# ETRX_Shield.net
KiCad netlist of a schematic drawn in Altium Designer
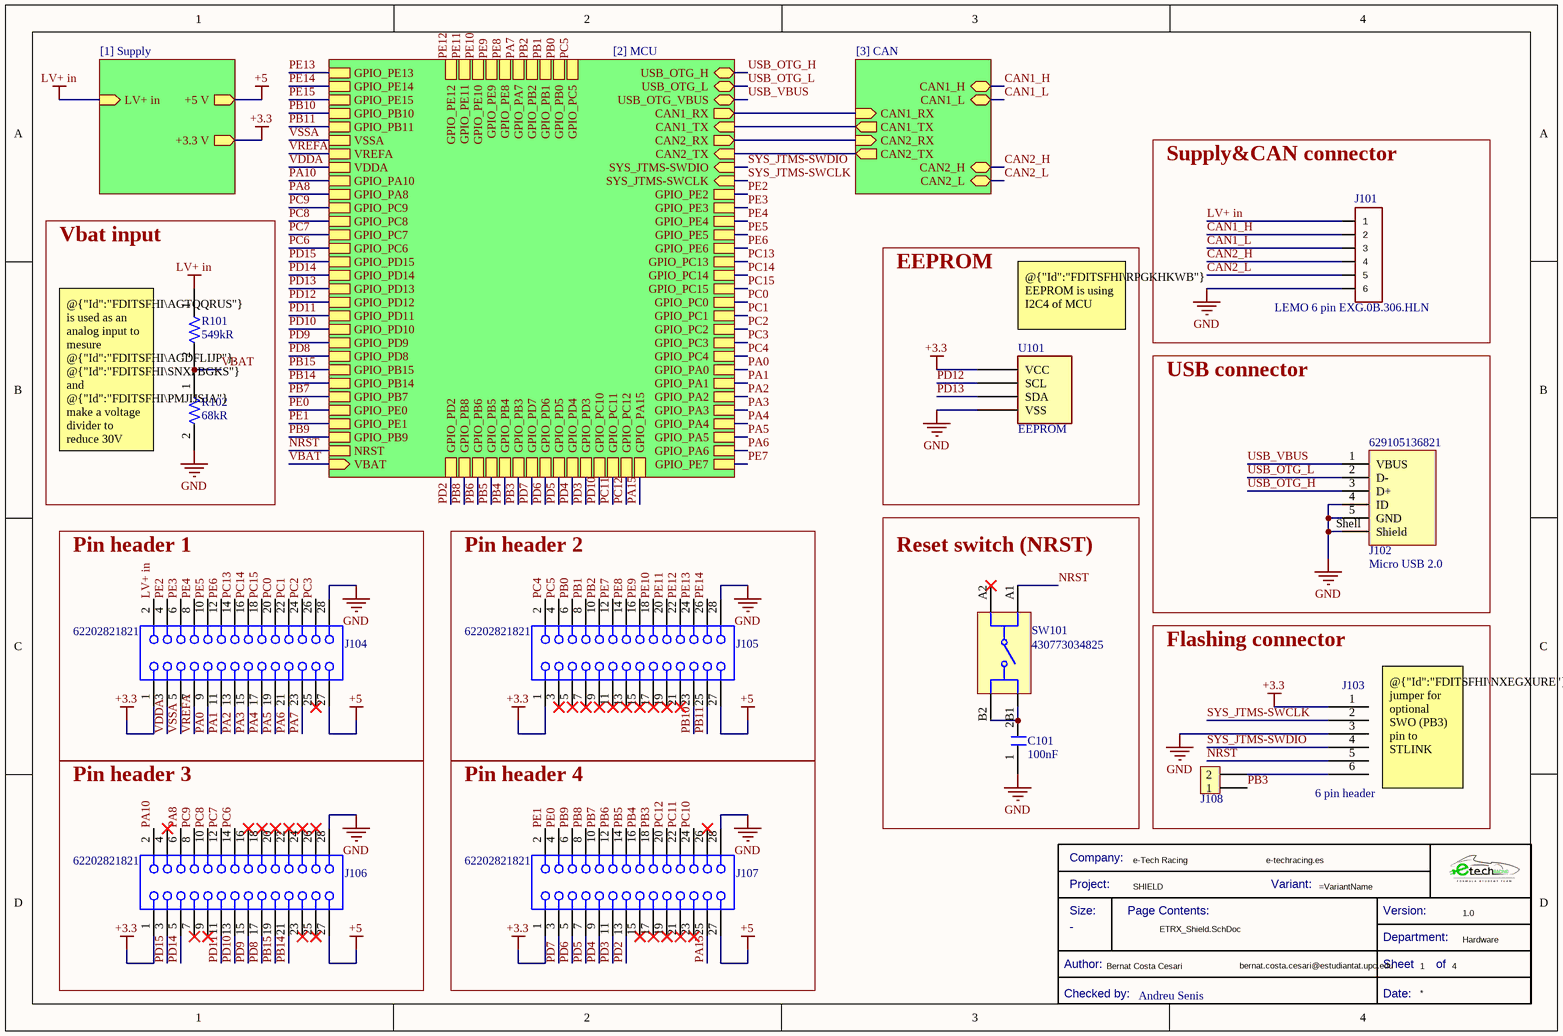
[diagram p0: ETRX_Shield.SchDoc]

(export (version "E")
  (design (tool "Eeschema 10.0.6"))
  (components
    (comp (ref "*")
      (value "Title Block_template")
      (description "Standard Title Block")
      (fields
        (field (name "SIZE") "-")
        (field (name ".CREATOR") "GP")
        (field (name ".PCBCHECK") "GP")
        (field (name ".SCHCHECK") "GP")
      )
      (libsource (lib "e-Tech_Racing") (part "Title Block_template"))
    )
    (comp (ref "C101")
      (value "885012208058")
      (footprint "C1206FNPC-RW")
      (description "Cap Cer 0.1UF 25V X7R 1206")
      (fields
        (field (name "MANUFACTURER") "Wurth Electronics")
        (field (name "TOLERANCE") "10%")
        (field (name "CAPACITANCE") "100nF")
        (field (name ".CREATOR") "DO")
      )
      (libsource (lib "Passives") (part "C100n-25V-1206FNPC-X7R"))
    )
    (comp (ref "J101")
      (value "LEMO 6 pin EXG.0B.306.HLN")
      (footprint "EXG.0B.306.HLN")
      (fields (field (name "MPN") "EXG.0B.306.HLN"))
      (libsource (lib "LEMO-EXG.0B.306.HLN") (part "EXG.0B.306.HLN"))
    )
    (comp (ref "J102")
      (value "629105136821")
      (footprint "629105136821")
      (description "WR-COM Micro USB 2.0 SMT Type B Horizontal 5 Contacts")
      (fields (field (name "MANUFACTURER") "Wurth Elektronik"))
      (libsource (lib "WR-USB") (part "629105136821"))
    )
    (comp (ref "J103") (value "6 pin header") (libsource (lib "CAN Transceiver") (part "6 pin header")))
    (comp (ref "J104")
      (value "62202821821")
      (footprint "62202821821")
      (description "WR-PHD Socket Header, THT, Vertical, pitch 1.27mm, 2 Row, 28P")
      (fields (field (name "MANUFACTURER") "Wurth Elektronik"))
      (libsource (lib "Altium_WR-PHD (rev22b)") (part "62202821821"))
    )
    (comp (ref "J105")
      (value "62202821821")
      (footprint "62202821821")
      (description "WR-PHD Socket Header, THT, Vertical, pitch 1.27mm, 2 Row, 28P")
      (fields (field (name "MANUFACTURER") "Wurth Elektronik"))
      (libsource (lib "Altium_WR-PHD (rev22b)") (part "62202821821"))
    )
    (comp (ref "J106")
      (value "62202821821")
      (footprint "62202821821")
      (description "WR-PHD Socket Header, THT, Vertical, pitch 1.27mm, 2 Row, 28P")
      (fields (field (name "MANUFACTURER") "Wurth Elektronik"))
      (libsource (lib "Altium_WR-PHD (rev22b)") (part "62202821821"))
    )
    (comp (ref "J107")
      (value "62202821821")
      (footprint "62202821821")
      (description "WR-PHD Socket Header, THT, Vertical, pitch 1.27mm, 2 Row, 28P")
      (fields (field (name "MANUFACTURER") "Wurth Elektronik"))
      (libsource (lib "Altium_WR-PHD (rev22b)") (part "62202821821"))
    )
    (comp (ref "J108")
      (value "282836-2")
      (footprint "J_screw_1x2")
      (description "Connector, Terminal Block; Wire Receptacle; 2 Pos.; 16-30 AWG; 0.197 in. CL; Sid")
      (libsource (lib "Electromechanical") (part "J_CON2x1"))
    )
    (comp (ref "R101") (value "549kR") (libsource (lib "Passives") (part "R549k - 0805")))
    (comp (ref "R102")
      (value "CR1206AFX-6802EAS")
      (footprint "R1206FTK-W")
      (description "Resistor, AS 1206 68k1% 250mW TC100")
      (fields
        (field (name "MANUFACTURER") "Bourns")
        (field (name "RESISTANCE") "68kR")
        (field (name ".CREATOR") "DO")
      )
      (libsource (lib "Passives") (part "R68k-1206FTK"))
    )
    (comp (ref "SW101")
      (value "430773034825")
      (footprint "WS-TASV_L6W6H3.4_4307x30348xx")
      (description "WS-TASV J-Hook SMT Hermetic Tact Switch, L6 x W6 x H3.4mm, 250g, SPST-NO, 12V, 50mA")
      (fields (field (name "MANUFACTURER") "Wurth Elektronik"))
      (libsource (lib "Altium_WS-SW bo") (part "430773034825"))
    )
    (comp (ref "U101") (value "EEPROM") (libsource (lib "CAN Transceiver") (part "I2C_EEPROM")))
  )
  (nets
    (net (code "1") (name "+3.3") (class "Default")
      (node (ref "J103") (pin "1") (pinfunction "1_1") (pintype "passive"))
      (node (ref "J104") (pin "1") (pinfunction "1_1") (pintype "passive"))
      (node (ref "J105") (pin "1") (pinfunction "1_1") (pintype "passive"))
      (node (ref "J106") (pin "1") (pinfunction "1_1") (pintype "passive"))
      (node (ref "J107") (pin "1") (pinfunction "1_1") (pintype "passive"))
      (node (ref "U101") (pin "1") (pinfunction "VCC_1") (pintype "passive"))
    )
    (net (code "2") (name "+5") (class "Default")
      (node (ref "J104") (pin "27") (pinfunction "27_27") (pintype "passive"))
      (node (ref "J105") (pin "27") (pinfunction "27_27") (pintype "passive"))
      (node (ref "J106") (pin "27") (pinfunction "27_27") (pintype "passive"))
      (node (ref "J107") (pin "27") (pinfunction "27_27") (pintype "passive"))
    )
    (net (code "3") (name "/CAN1_H") (class "Default")
      (node (ref "J101") (pin "2") (pinfunction "2_2") (pintype "passive"))
    )
    (net (code "4") (name "/CAN1_L") (class "Default")
      (node (ref "J101") (pin "3") (pinfunction "3_3") (pintype "passive"))
    )
    (net (code "7") (name "/CAN2_H") (class "Default")
      (node (ref "J101") (pin "4") (pinfunction "4_4") (pintype "passive"))
    )
    (net (code "8") (name "/CAN2_L") (class "Default")
      (node (ref "J101") (pin "5") (pinfunction "5_5") (pintype "passive"))
    )
    (net (code "11") (name "/NRST") (class "Default")
      (node (ref "J103") (pin "5") (pinfunction "5_5") (pintype "passive"))
      (node (ref "SW101") (pin "A1") (pinfunction "A1_A1") (pintype "passive"))
    )
    (net (code "12") (name "/PA0") (class "Default")
      (node (ref "J104") (pin "9") (pinfunction "9_9") (pintype "passive"))
    )
    (net (code "13") (name "/PA1") (class "Default")
      (node (ref "J104") (pin "11") (pinfunction "11_11") (pintype "passive"))
    )
    (net (code "14") (name "/PA2") (class "Default")
      (node (ref "J104") (pin "13") (pinfunction "13_13") (pintype "passive"))
    )
    (net (code "15") (name "/PA3") (class "Default")
      (node (ref "J104") (pin "15") (pinfunction "15_15") (pintype "passive"))
    )
    (net (code "16") (name "/PA4") (class "Default")
      (node (ref "J104") (pin "17") (pinfunction "17_17") (pintype "passive"))
    )
    (net (code "17") (name "/PA5") (class "Default")
      (node (ref "J104") (pin "19") (pinfunction "19_19") (pintype "passive"))
    )
    (net (code "18") (name "/PA6") (class "Default")
      (node (ref "J104") (pin "21") (pinfunction "21_21") (pintype "passive"))
    )
    (net (code "19") (name "/PA7") (class "Default")
      (node (ref "J104") (pin "23") (pinfunction "23_23") (pintype "passive"))
    )
    (net (code "20") (name "/PA8") (class "Default")
      (node (ref "J106") (pin "6") (pinfunction "6_6") (pintype "passive"))
    )
    (net (code "21") (name "/PA10") (class "Default")
      (node (ref "J106") (pin "2") (pinfunction "2_2") (pintype "passive"))
    )
    (net (code "22") (name "/PA15") (class "Default")
      (node (ref "J107") (pin "25") (pinfunction "25_25") (pintype "passive"))
    )
    (net (code "23") (name "/PB0") (class "Default")
      (node (ref "J105") (pin "6") (pinfunction "6_6") (pintype "passive"))
    )
    (net (code "24") (name "/PB1") (class "Default")
      (node (ref "J105") (pin "8") (pinfunction "8_8") (pintype "passive"))
    )
    (net (code "25") (name "/PB2") (class "Default")
      (node (ref "J105") (pin "10") (pinfunction "10_10") (pintype "passive"))
    )
    (net (code "26") (name "/PB3") (class "Default")
      (node (ref "J107") (pin "18") (pinfunction "18_18") (pintype "passive"))
      (node (ref "J108") (pin "1") (pinfunction "1_1") (pintype "passive"))
    )
    (net (code "27") (name "/PB4") (class "Default")
      (node (ref "J107") (pin "16") (pinfunction "16_16") (pintype "passive"))
    )
    (net (code "28") (name "/PB5") (class "Default")
      (node (ref "J107") (pin "14") (pinfunction "14_14") (pintype "passive"))
    )
    (net (code "29") (name "/PB6") (class "Default")
      (node (ref "J107") (pin "12") (pinfunction "12_12") (pintype "passive"))
    )
    (net (code "30") (name "/PB7") (class "Default")
      (node (ref "J107") (pin "10") (pinfunction "10_10") (pintype "passive"))
    )
    (net (code "31") (name "/PB8") (class "Default")
      (node (ref "J107") (pin "8") (pinfunction "8_8") (pintype "passive"))
    )
    (net (code "32") (name "/PB9") (class "Default")
      (node (ref "J107") (pin "6") (pinfunction "6_6") (pintype "passive"))
    )
    (net (code "33") (name "/PB10") (class "Default")
      (node (ref "J105") (pin "23") (pinfunction "23_23") (pintype "passive"))
    )
    (net (code "34") (name "/PB11") (class "Default")
      (node (ref "J105") (pin "25") (pinfunction "25_25") (pintype "passive"))
    )
    (net (code "35") (name "/PB14") (class "Default")
      (node (ref "J106") (pin "21") (pinfunction "21_21") (pintype "passive"))
    )
    (net (code "36") (name "/PB15") (class "Default")
      (node (ref "J106") (pin "19") (pinfunction "19_19") (pintype "passive"))
    )
    (net (code "37") (name "/PC0") (class "Default")
      (node (ref "J104") (pin "20") (pinfunction "20_20") (pintype "passive"))
    )
    (net (code "38") (name "/PC1") (class "Default")
      (node (ref "J104") (pin "22") (pinfunction "22_22") (pintype "passive"))
    )
    (net (code "39") (name "/PC2") (class "Default")
      (node (ref "J104") (pin "24") (pinfunction "24_24") (pintype "passive"))
    )
    (net (code "40") (name "/PC3") (class "Default")
      (node (ref "J104") (pin "26") (pinfunction "26_26") (pintype "passive"))
    )
    (net (code "41") (name "/PC4") (class "Default")
      (node (ref "J105") (pin "2") (pinfunction "2_2") (pintype "passive"))
    )
    (net (code "42") (name "/PC5") (class "Default")
      (node (ref "J105") (pin "4") (pinfunction "4_4") (pintype "passive"))
    )
    (net (code "43") (name "/PC6") (class "Default")
      (node (ref "J106") (pin "14") (pinfunction "14_14") (pintype "passive"))
    )
    (net (code "44") (name "/PC7") (class "Default")
      (node (ref "J106") (pin "12") (pinfunction "12_12") (pintype "passive"))
    )
    (net (code "45") (name "/PC8") (class "Default")
      (node (ref "J106") (pin "10") (pinfunction "10_10") (pintype "passive"))
    )
    (net (code "46") (name "/PC9") (class "Default")
      (node (ref "J106") (pin "8") (pinfunction "8_8") (pintype "passive"))
    )
    (net (code "47") (name "/PC10") (class "Default")
      (node (ref "J107") (pin "24") (pinfunction "24_24") (pintype "passive"))
    )
    (net (code "48") (name "/PC11") (class "Default")
      (node (ref "J107") (pin "22") (pinfunction "22_22") (pintype "passive"))
    )
    (net (code "49") (name "/PC12") (class "Default")
      (node (ref "J107") (pin "20") (pinfunction "20_20") (pintype "passive"))
    )
    (net (code "50") (name "/PC13") (class "Default")
      (node (ref "J104") (pin "14") (pinfunction "14_14") (pintype "passive"))
    )
    (net (code "51") (name "/PC14") (class "Default")
      (node (ref "J104") (pin "16") (pinfunction "16_16") (pintype "passive"))
    )
    (net (code "52") (name "/PC15") (class "Default")
      (node (ref "J104") (pin "18") (pinfunction "18_18") (pintype "passive"))
    )
    (net (code "53") (name "/PD2") (class "Default")
      (node (ref "J107") (pin "13") (pinfunction "13_13") (pintype "passive"))
    )
    (net (code "54") (name "/PD3") (class "Default")
      (node (ref "J107") (pin "11") (pinfunction "11_11") (pintype "passive"))
    )
    (net (code "55") (name "/PD4") (class "Default")
      (node (ref "J107") (pin "9") (pinfunction "9_9") (pintype "passive"))
    )
    (net (code "56") (name "/PD5") (class "Default")
      (node (ref "J107") (pin "7") (pinfunction "7_7") (pintype "passive"))
    )
    (net (code "57") (name "/PD6") (class "Default")
      (node (ref "J107") (pin "5") (pinfunction "5_5") (pintype "passive"))
    )
    (net (code "58") (name "/PD7") (class "Default")
      (node (ref "J107") (pin "3") (pinfunction "3_3") (pintype "passive"))
    )
    (net (code "59") (name "/PD8") (class "Default")
      (node (ref "J106") (pin "17") (pinfunction "17_17") (pintype "passive"))
    )
    (net (code "60") (name "/PD9") (class "Default")
      (node (ref "J106") (pin "15") (pinfunction "15_15") (pintype "passive"))
    )
    (net (code "61") (name "/PD10") (class "Default")
      (node (ref "J106") (pin "13") (pinfunction "13_13") (pintype "passive"))
    )
    (net (code "62") (name "/PD11") (class "Default")
      (node (ref "J106") (pin "11") (pinfunction "11_11") (pintype "passive"))
    )
    (net (code "63") (name "/PD12") (class "Default")
      (node (ref "U101") (pin "2") (pinfunction "SCL_2") (pintype "passive"))
    )
    (net (code "64") (name "/PD13") (class "Default")
      (node (ref "U101") (pin "3") (pinfunction "SDA_3") (pintype "passive"))
    )
    (net (code "65") (name "/PD14") (class "Default")
      (node (ref "J106") (pin "5") (pinfunction "5_5") (pintype "passive"))
    )
    (net (code "66") (name "/PD15") (class "Default")
      (node (ref "J106") (pin "3") (pinfunction "3_3") (pintype "passive"))
    )
    (net (code "67") (name "/PE0") (class "Default")
      (node (ref "J107") (pin "4") (pinfunction "4_4") (pintype "passive"))
    )
    (net (code "68") (name "/PE1") (class "Default")
      (node (ref "J107") (pin "2") (pinfunction "2_2") (pintype "passive"))
    )
    (net (code "69") (name "/PE2") (class "Default")
      (node (ref "J104") (pin "4") (pinfunction "4_4") (pintype "passive"))
    )
    (net (code "70") (name "/PE3") (class "Default")
      (node (ref "J104") (pin "6") (pinfunction "6_6") (pintype "passive"))
    )
    (net (code "71") (name "/PE4") (class "Default")
      (node (ref "J104") (pin "8") (pinfunction "8_8") (pintype "passive"))
    )
    (net (code "72") (name "/PE5") (class "Default")
      (node (ref "J104") (pin "10") (pinfunction "10_10") (pintype "passive"))
    )
    (net (code "73") (name "/PE6") (class "Default")
      (node (ref "J104") (pin "12") (pinfunction "12_12") (pintype "passive"))
    )
    (net (code "74") (name "/PE7") (class "Default")
      (node (ref "J105") (pin "12") (pinfunction "12_12") (pintype "passive"))
    )
    (net (code "75") (name "/PE8") (class "Default")
      (node (ref "J105") (pin "14") (pinfunction "14_14") (pintype "passive"))
    )
    (net (code "76") (name "/PE9") (class "Default")
      (node (ref "J105") (pin "16") (pinfunction "16_16") (pintype "passive"))
    )
    (net (code "77") (name "/PE10") (class "Default")
      (node (ref "J105") (pin "18") (pinfunction "18_18") (pintype "passive"))
    )
    (net (code "78") (name "/PE11") (class "Default")
      (node (ref "J105") (pin "20") (pinfunction "20_20") (pintype "passive"))
    )
    (net (code "79") (name "/PE12") (class "Default")
      (node (ref "J105") (pin "22") (pinfunction "22_22") (pintype "passive"))
    )
    (net (code "80") (name "/PE13") (class "Default")
      (node (ref "J105") (pin "24") (pinfunction "24_24") (pintype "passive"))
    )
    (net (code "81") (name "/PE14") (class "Default")
      (node (ref "J105") (pin "26") (pinfunction "26_26") (pintype "passive"))
    )
    (net (code "83") (name "/SYS_JTMS-SWCLK") (class "Default")
      (node (ref "J103") (pin "2") (pinfunction "2_2") (pintype "passive"))
    )
    (net (code "84") (name "/SYS_JTMS-SWDIO") (class "Default")
      (node (ref "J103") (pin "4") (pinfunction "4_4") (pintype "passive"))
    )
    (net (code "85") (name "/USB_OTG_H") (class "Default")
      (node (ref "J102") (pin "3") (pinfunction "D+_3") (pintype "passive"))
    )
    (net (code "86") (name "/USB_OTG_L") (class "Default")
      (node (ref "J102") (pin "2") (pinfunction "D-_2") (pintype "passive"))
    )
    (net (code "87") (name "/USB_VBUS") (class "Default")
      (node (ref "J102") (pin "1") (pinfunction "VBUS_1") (pintype "passive"))
    )
    (net (code "88") (name "/VBAT") (class "Default")
      (node (ref "R101") (pin "2") (pinfunction "2_2") (pintype "passive"))
      (node (ref "R102") (pin "1") (pinfunction "1_1") (pintype "passive"))
    )
    (net (code "89") (name "/VDDA") (class "Default")
      (node (ref "J104") (pin "3") (pinfunction "3_3") (pintype "passive"))
    )
    (net (code "90") (name "/VREFA") (class "Default")
      (node (ref "J104") (pin "7") (pinfunction "7_7") (pintype "passive"))
    )
    (net (code "91") (name "/VSSA") (class "Default")
      (node (ref "J104") (pin "5") (pinfunction "5_5") (pintype "passive"))
    )
    (net (code "92") (name "GND") (class "Default")
      (node (ref "C101") (pin "1") (pinfunction "1_1") (pintype "passive"))
      (node (ref "J101") (pin "6") (pinfunction "6_6") (pintype "passive"))
      (node (ref "J102") (pin "4") (pinfunction "ID_4") (pintype "passive"))
      (node (ref "J102") (pin "5") (pinfunction "GND_5") (pintype "passive"))
      (node (ref "J102") (pin "Shell") (pinfunction "Shield_Shell") (pintype "passive"))
      (node (ref "J103") (pin "3") (pinfunction "3_3") (pintype "passive"))
      (node (ref "J104") (pin "28") (pinfunction "28_28") (pintype "passive"))
      (node (ref "J105") (pin "28") (pinfunction "28_28") (pintype "passive"))
      (node (ref "J106") (pin "28") (pinfunction "28_28") (pintype "passive"))
      (node (ref "J107") (pin "28") (pinfunction "28_28") (pintype "passive"))
      (node (ref "R102") (pin "2") (pinfunction "2_2") (pintype "passive"))
      (node (ref "U101") (pin "4") (pinfunction "VSS_4") (pintype "power_in"))
    )
    (net (code "93") (name "LV+ in") (class "Default")
      (node (ref "J101") (pin "1") (pinfunction "1_1") (pintype "passive"))
      (node (ref "J104") (pin "2") (pinfunction "2_2") (pintype "passive"))
      (node (ref "R101") (pin "1") (pinfunction "1_1") (pintype "passive"))
    )
    (net (code "94") (name "Net-(C101-Pad2)") (class "Default")
      (node (ref "C101") (pin "2") (pinfunction "2_2") (pintype "passive"))
      (node (ref "SW101") (pin "B1") (pinfunction "B1_B1") (pintype "passive"))
      (node (ref "SW101") (pin "B2") (pinfunction "B2_B2") (pintype "passive"))
    )
    (net (code "95") (name "Net-(J103-Pad6)") (class "Default")
      (node (ref "J103") (pin "6") (pinfunction "6_6") (pintype "passive"))
      (node (ref "J108") (pin "2") (pinfunction "2_2") (pintype "passive"))
    )
    (net (code "96") (name "unconnected-(J104-Pad25)") (class "Default")
      (node (ref "J104") (pin "25") (pinfunction "25_25") (pintype "passive+no_connect"))
    )
    (net (code "97") (name "unconnected-(J105-Pad3)") (class "Default")
      (node (ref "J105") (pin "3") (pinfunction "3_3") (pintype "passive+no_connect"))
    )
    (net (code "98") (name "unconnected-(J105-Pad5)") (class "Default")
      (node (ref "J105") (pin "5") (pinfunction "5_5") (pintype "passive+no_connect"))
    )
    (net (code "99") (name "unconnected-(J105-Pad7)") (class "Default")
      (node (ref "J105") (pin "7") (pinfunction "7_7") (pintype "passive+no_connect"))
    )
    (net (code "100") (name "unconnected-(J105-Pad9)") (class "Default")
      (node (ref "J105") (pin "9") (pinfunction "9_9") (pintype "passive+no_connect"))
    )
    (net (code "101") (name "unconnected-(J105-Pad11)") (class "Default")
      (node (ref "J105") (pin "11") (pinfunction "11_11") (pintype "passive+no_connect"))
    )
    (net (code "102") (name "unconnected-(J105-Pad13)") (class "Default")
      (node (ref "J105") (pin "13") (pinfunction "13_13") (pintype "passive+no_connect"))
    )
    (net (code "103") (name "unconnected-(J105-Pad15)") (class "Default")
      (node (ref "J105") (pin "15") (pinfunction "15_15") (pintype "passive+no_connect"))
    )
    (net (code "104") (name "unconnected-(J105-Pad17)") (class "Default")
      (node (ref "J105") (pin "17") (pinfunction "17_17") (pintype "passive+no_connect"))
    )
    (net (code "105") (name "unconnected-(J105-Pad19)") (class "Default")
      (node (ref "J105") (pin "19") (pinfunction "19_19") (pintype "passive+no_connect"))
    )
    (net (code "106") (name "unconnected-(J105-Pad21)") (class "Default")
      (node (ref "J105") (pin "21") (pinfunction "21_21") (pintype "passive+no_connect"))
    )
    (net (code "107") (name "unconnected-(J106-Pad4)") (class "Default")
      (node (ref "J106") (pin "4") (pinfunction "4_4") (pintype "passive+no_connect"))
    )
    (net (code "108") (name "unconnected-(J106-Pad7)") (class "Default")
      (node (ref "J106") (pin "7") (pinfunction "7_7") (pintype "passive+no_connect"))
    )
    (net (code "109") (name "unconnected-(J106-Pad9)") (class "Default")
      (node (ref "J106") (pin "9") (pinfunction "9_9") (pintype "passive+no_connect"))
    )
    (net (code "110") (name "unconnected-(J106-Pad16)") (class "Default")
      (node (ref "J106") (pin "16") (pinfunction "16_16") (pintype "passive+no_connect"))
    )
    (net (code "111") (name "unconnected-(J106-Pad18)") (class "Default")
      (node (ref "J106") (pin "18") (pinfunction "18_18") (pintype "passive+no_connect"))
    )
    (net (code "112") (name "unconnected-(J106-Pad20)") (class "Default")
      (node (ref "J106") (pin "20") (pinfunction "20_20") (pintype "passive+no_connect"))
    )
    (net (code "113") (name "unconnected-(J106-Pad22)") (class "Default")
      (node (ref "J106") (pin "22") (pinfunction "22_22") (pintype "passive+no_connect"))
    )
    (net (code "114") (name "unconnected-(J106-Pad23)") (class "Default")
      (node (ref "J106") (pin "23") (pinfunction "23_23") (pintype "passive+no_connect"))
    )
    (net (code "115") (name "unconnected-(J106-Pad24)") (class "Default")
      (node (ref "J106") (pin "24") (pinfunction "24_24") (pintype "passive+no_connect"))
    )
    (net (code "116") (name "unconnected-(J106-Pad25)") (class "Default")
      (node (ref "J106") (pin "25") (pinfunction "25_25") (pintype "passive+no_connect"))
    )
    (net (code "117") (name "unconnected-(J106-Pad26)") (class "Default")
      (node (ref "J106") (pin "26") (pinfunction "26_26") (pintype "passive+no_connect"))
    )
    (net (code "118") (name "unconnected-(J107-Pad15)") (class "Default")
      (node (ref "J107") (pin "15") (pinfunction "15_15") (pintype "passive+no_connect"))
    )
    (net (code "119") (name "unconnected-(J107-Pad17)") (class "Default")
      (node (ref "J107") (pin "17") (pinfunction "17_17") (pintype "passive+no_connect"))
    )
    (net (code "120") (name "unconnected-(J107-Pad19)") (class "Default")
      (node (ref "J107") (pin "19") (pinfunction "19_19") (pintype "passive+no_connect"))
    )
    (net (code "121") (name "unconnected-(J107-Pad21)") (class "Default")
      (node (ref "J107") (pin "21") (pinfunction "21_21") (pintype "passive+no_connect"))
    )
    (net (code "122") (name "unconnected-(J107-Pad23)") (class "Default")
      (node (ref "J107") (pin "23") (pinfunction "23_23") (pintype "passive+no_connect"))
    )
    (net (code "123") (name "unconnected-(J107-Pad26)") (class "Default")
      (node (ref "J107") (pin "26") (pinfunction "26_26") (pintype "passive+no_connect"))
    )
    (net (code "124") (name "unconnected-(SW101-PadA2)") (class "Default")
      (node (ref "SW101") (pin "A2") (pinfunction "A2_A2") (pintype "passive+no_connect"))
    )
  )
)
